# sparrow_ble.net
KiCad netlist of a schematic drawn in EAGLE
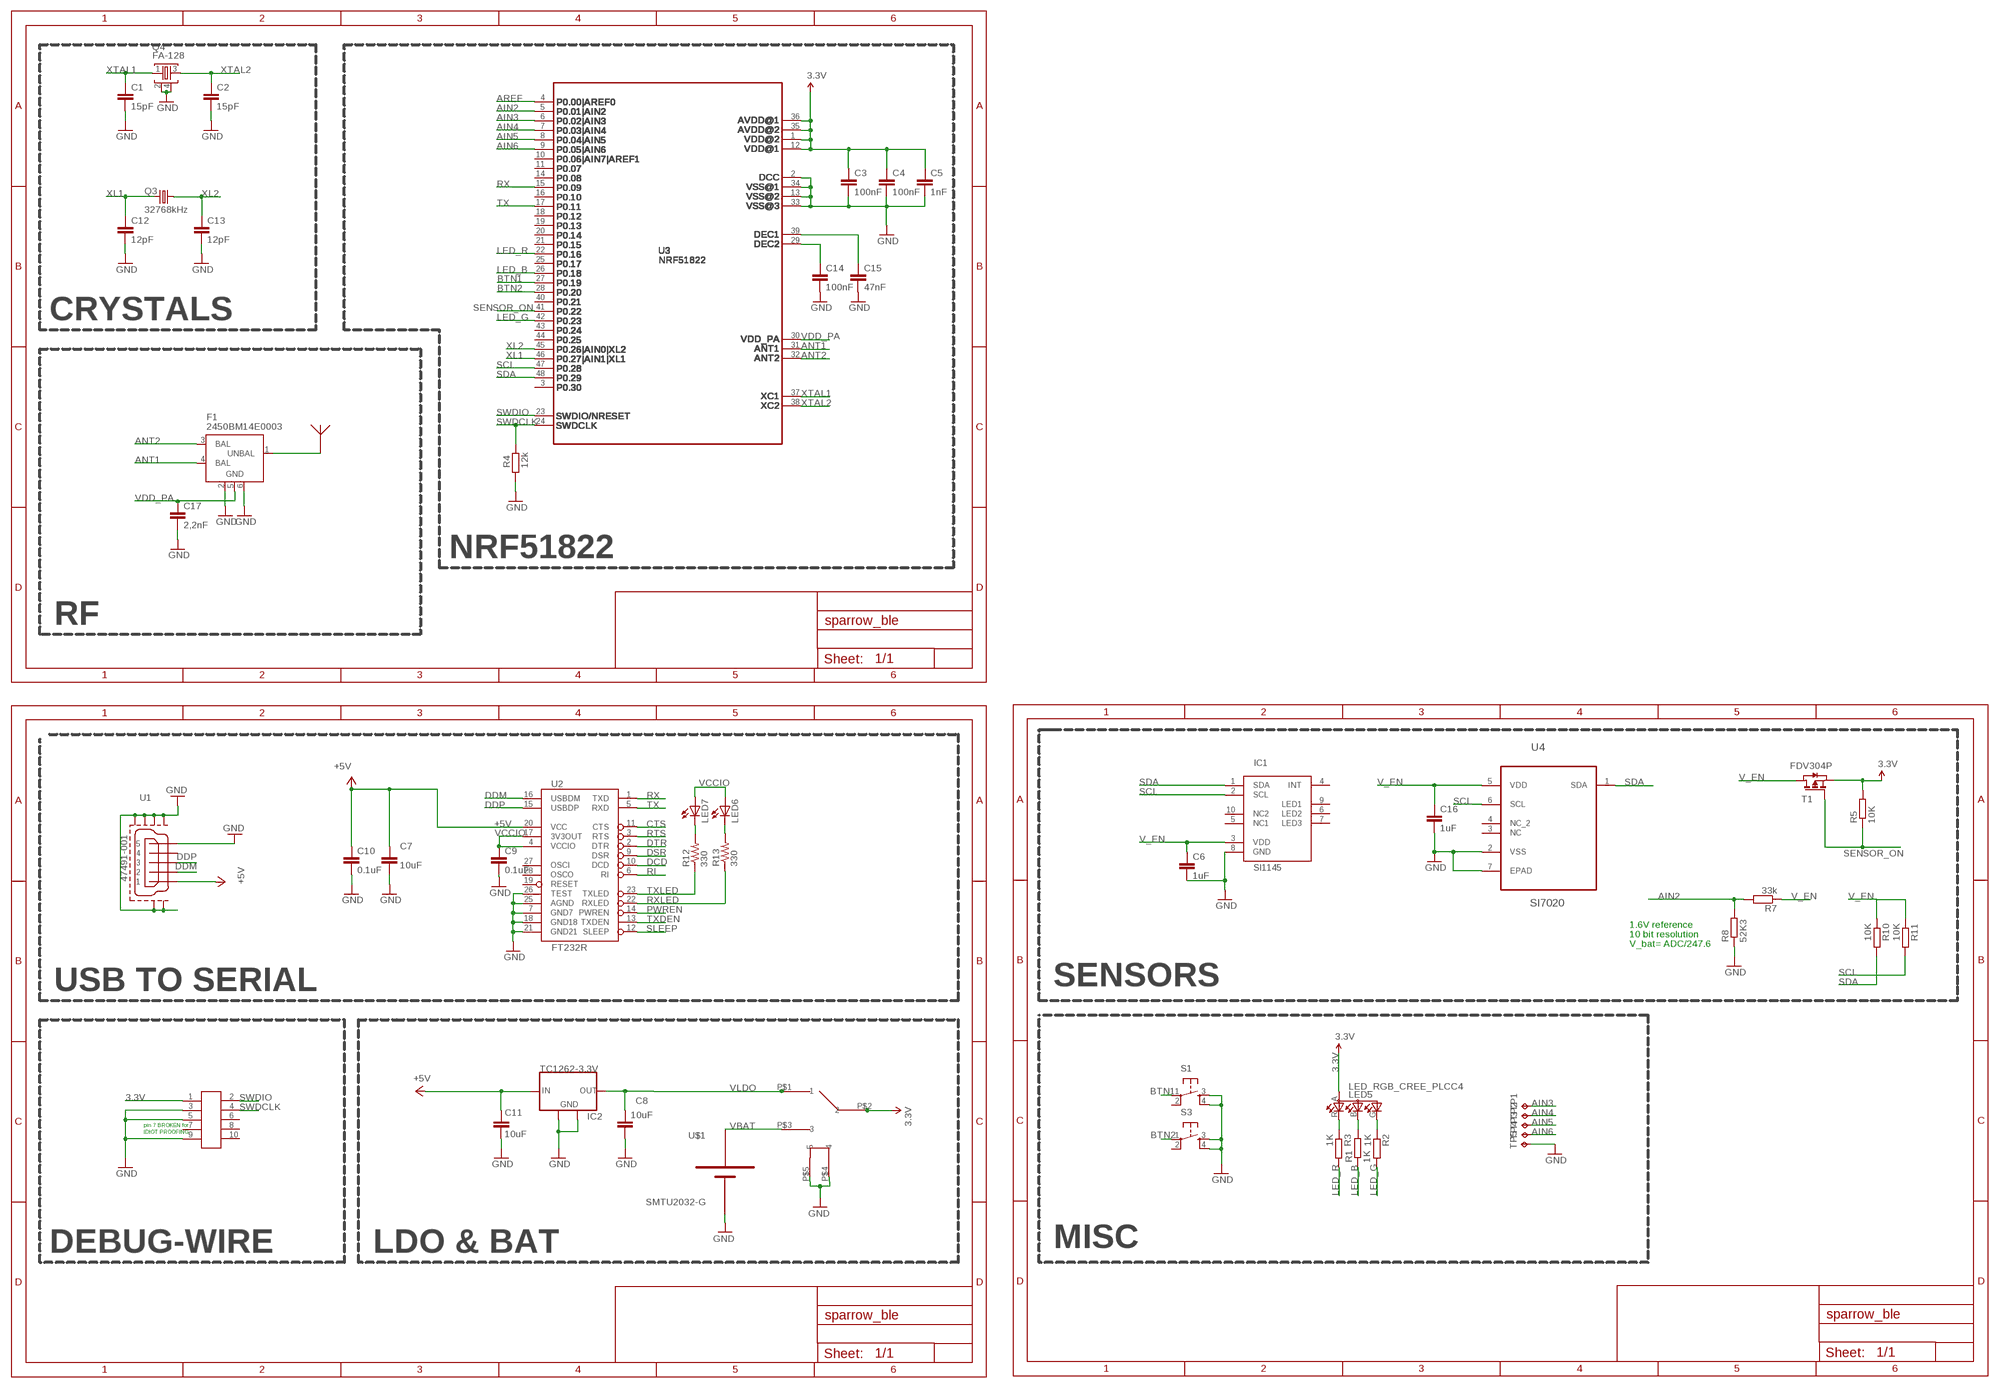
[diagram p0: schematic, sheet 1]

(export (version "E")
  (design (tool "Eeschema 10.0.6"))
  (components
    (comp (ref "C1")
      (value "15pF")
      (footprint "eagle-import:C0402")
      (libsource (lib "eagle-import") (part "resistor_C-EUC0402"))
    )
    (comp (ref "C2")
      (value "15pF")
      (footprint "eagle-import:C0402")
      (libsource (lib "eagle-import") (part "resistor_C-EUC0402"))
    )
    (comp (ref "C3")
      (value "100nF")
      (footprint "eagle-import:C0402")
      (libsource (lib "eagle-import") (part "resistor_C-EUC0402"))
    )
    (comp (ref "C4")
      (value "100nF")
      (footprint "eagle-import:C0402")
      (libsource (lib "eagle-import") (part "resistor_C-EUC0402"))
    )
    (comp (ref "C5")
      (value "1nF")
      (footprint "eagle-import:C0402")
      (libsource (lib "eagle-import") (part "resistor_C-EUC0402"))
    )
    (comp (ref "C6")
      (value "1uF")
      (footprint "eagle-import:C0402")
      (libsource (lib "eagle-import") (part "resistor_C-EUC0402"))
    )
    (comp (ref "C7")
      (value "10uF")
      (footprint "eagle-import:C0402")
      (libsource (lib "eagle-import") (part "C-EUC0402"))
    )
    (comp (ref "C8")
      (value "10uF")
      (footprint "eagle-import:C0402")
      (libsource (lib "eagle-import") (part "C-EUC0402"))
    )
    (comp (ref "C9")
      (value "0.1uF")
      (footprint "eagle-import:0402-CAP")
      (libsource (lib "eagle-import") (part "CAP0402-CAP"))
    )
    (comp (ref "C10")
      (value "0.1uF")
      (footprint "eagle-import:0402-CAP")
      (libsource (lib "eagle-import") (part "CAP0402-CAP"))
    )
    (comp (ref "C11")
      (value "10uF")
      (footprint "eagle-import:C0402")
      (libsource (lib "eagle-import") (part "C-EUC0402"))
    )
    (comp (ref "C12")
      (value "12pF")
      (footprint "eagle-import:C0402")
      (libsource (lib "eagle-import") (part "resistor_C-EUC0402"))
    )
    (comp (ref "C13")
      (value "12pF")
      (footprint "eagle-import:C0402")
      (libsource (lib "eagle-import") (part "resistor_C-EUC0402"))
    )
    (comp (ref "C14")
      (value "100nF")
      (footprint "eagle-import:C0402")
      (libsource (lib "eagle-import") (part "resistor_C-EUC0402"))
    )
    (comp (ref "C15")
      (value "47nF")
      (footprint "eagle-import:C0402")
      (libsource (lib "eagle-import") (part "resistor_C-EUC0402"))
    )
    (comp (ref "C16")
      (value "1uF")
      (footprint "eagle-import:C0402")
      (libsource (lib "eagle-import") (part "resistor_C-EUC0402"))
    )
    (comp (ref "C17")
      (value "2,2nF")
      (footprint "eagle-import:C0402")
      (libsource (lib "eagle-import") (part "resistor_C-EUC0402"))
    )
    (comp (ref "F1")
      (value "2450BM14E0003")
      (footprint "eagle-import:2450BM15A0002")
      (libsource (lib "eagle-import") (part "2450BM15A0002"))
    )
    (comp (ref "IC1")
      (value "SI1145")
      (footprint "eagle-import:QFN10")
      (libsource (lib "eagle-import") (part "SI1145"))
    )
    (comp (ref "IC2")
      (value "TC1262-3.3V")
      (footprint "eagle-import:SOT223")
      (libsource (lib "eagle-import") (part "MCP1825S-SOT223"))
    )
    (comp (ref "J3")
      (value "SMALL_HEADER_5X2")
      (footprint "eagle-import:SAMTEC_5X2")
      (libsource (lib "eagle-import") (part "SMALL_HEADER_5X2"))
    )
    (comp (ref "LED5")
      (value "LED_RGB_CREE_PLCC4")
      (footprint "eagle-import:P-LCC-4-4")
      (libsource (lib "eagle-import") (part "LED_RGB_CREE_PLCC4"))
    )
    (comp (ref "LED6")
      (value "LEDCHIP-LED0603")
      (footprint "eagle-import:CHIP-LED0603")
      (libsource (lib "eagle-import") (part "LEDCHIP-LED0603"))
    )
    (comp (ref "LED7")
      (value "LEDCHIP-LED0603")
      (footprint "eagle-import:CHIP-LED0603")
      (libsource (lib "eagle-import") (part "LEDCHIP-LED0603"))
    )
    (comp (ref "Q3")
      (value "32768kHz")
      (footprint "eagle-import:FC-12M")
      (libsource (lib "eagle-import") (part "FC-12M"))
    )
    (comp (ref "Q4")
      (value "FA-128")
      (footprint "eagle-import:FA-128")
      (libsource (lib "eagle-import") (part "FA-128"))
    )
    (comp (ref "R1")
      (value "1K")
      (footprint "eagle-import:R0402")
      (libsource (lib "eagle-import") (part "R-EU_R0402"))
    )
    (comp (ref "R2")
      (value "1K")
      (footprint "eagle-import:R0402")
      (libsource (lib "eagle-import") (part "R-EU_R0402"))
    )
    (comp (ref "R3")
      (value "1K")
      (footprint "eagle-import:R0402")
      (libsource (lib "eagle-import") (part "R-EU_R0402"))
    )
    (comp (ref "R4")
      (value "12k")
      (footprint "eagle-import:R0402")
      (libsource (lib "eagle-import") (part "resistor_R-EU_R0402"))
    )
    (comp (ref "R5")
      (value "10K")
      (footprint "eagle-import:R0402")
      (libsource (lib "eagle-import") (part "resistor_R-EU_R0402"))
    )
    (comp (ref "R7")
      (value "33k")
      (footprint "eagle-import:R0402")
      (libsource (lib "eagle-import") (part "resistor_R-EU_R0402"))
    )
    (comp (ref "R8")
      (value "52K3")
      (footprint "eagle-import:R0402")
      (libsource (lib "eagle-import") (part "resistor_R-EU_R0402"))
    )
    (comp (ref "R10")
      (value "10K")
      (footprint "eagle-import:R0402")
      (libsource (lib "eagle-import") (part "resistor_R-EU_R0402"))
    )
    (comp (ref "R11")
      (value "10K")
      (footprint "eagle-import:R0402")
      (libsource (lib "eagle-import") (part "resistor_R-EU_R0402"))
    )
    (comp (ref "R12")
      (value "330")
      (footprint "eagle-import:0402-RES")
      (libsource (lib "eagle-import") (part "RESISTOR0402-RES"))
    )
    (comp (ref "R13")
      (value "330")
      (footprint "eagle-import:0402-RES")
      (libsource (lib "eagle-import") (part "RESISTOR0402-RES"))
    )
    (comp (ref "S1")
      (value "TAC_SWITCHSMD")
      (footprint "eagle-import:TACTILE-SWITCH-SMD")
      (libsource (lib "eagle-import") (part "TAC_SWITCHSMD"))
    )
    (comp (ref "S3")
      (value "TAC_SWITCHSMD")
      (footprint "eagle-import:TACTILE-SWITCH-SMD")
      (libsource (lib "eagle-import") (part "TAC_SWITCHSMD"))
    )
    (comp (ref "T1")
      (value "FDV304P")
      (footprint "eagle-import:SOT-23")
      (libsource (lib "eagle-import") (part "PMOSSOT23"))
    )
    (comp (ref "TP1")
      (value "TPTP16R")
      (footprint "eagle-import:TP16R")
      (libsource (lib "eagle-import") (part "TPTP16R"))
    )
    (comp (ref "TP2")
      (value "TPTP16R")
      (footprint "eagle-import:TP16R")
      (libsource (lib "eagle-import") (part "TPTP16R"))
    )
    (comp (ref "TP3")
      (value "TPTP16R")
      (footprint "eagle-import:TP16R")
      (libsource (lib "eagle-import") (part "TPTP16R"))
    )
    (comp (ref "TP4")
      (value "TPTP16R")
      (footprint "eagle-import:TP16R")
      (libsource (lib "eagle-import") (part "TPTP16R"))
    )
    (comp (ref "TP5")
      (value "TPTP16R")
      (footprint "eagle-import:TP16R")
      (libsource (lib "eagle-import") (part "TPTP16R"))
    )
    (comp (ref "U$1")
      (value "SMTU2032-G")
      (footprint "eagle-import:SMTU2032-G")
      (libsource (lib "eagle-import") (part "SMTU2032-G"))
    )
    (comp (ref "U$2")
      (value "SWITCH")
      (footprint "eagle-import:PCM12")
      (libsource (lib "eagle-import") (part "SWITCH"))
    )
    (comp (ref "U1")
      (value "47491-001")
      (footprint "eagle-import:47491-0001")
      (libsource (lib "eagle-import") (part "47491-001"))
    )
    (comp (ref "U2")
      (value "FT232R")
      (footprint "eagle-import:SSOP28DB")
      (libsource (lib "eagle-import") (part "FT232RLSSOP"))
    )
    (comp (ref "U3")
      (value "NRF51822")
      (footprint "eagle-import:NRF51822-QFN48")
      (libsource (lib "eagle-import") (part "NRF51822"))
    )
    (comp (ref "U4")
      (value "SI7020")
      (footprint "eagle-import:DFN300X300X110-7N")
      (fields (field (name "MPN") "SHT21"))
      (libsource (lib "eagle-import") (part "SHT21"))
    )
    (comp (ref "U8")
      (value "ANTENNA")
      (footprint "eagle-import:ANTPACK")
      (libsource (lib "eagle-import") (part "ANTENNA"))
    )
  )
  (nets
    (net (code "1") (name "+5V") (class "Default")
      (node (ref "C10") (pin "1") (pinfunction "1_1") (pintype "passive"))
      (node (ref "C11") (pin "1") (pinfunction "1_1") (pintype "passive"))
      (node (ref "C7") (pin "1") (pinfunction "1_1") (pintype "passive"))
      (node (ref "IC2") (pin "1") (pinfunction "IN_1") (pintype "input"))
      (node (ref "U1") (pin "1") (pinfunction "1_1") (pintype "input"))
      (node (ref "U2") (pin "20") (pinfunction "VCC_20") (pintype "power_in"))
    )
    (net (code "2") (name "/AIN2") (class "Default")
      (node (ref "R7") (pin "2") (pinfunction "2_2") (pintype "passive"))
      (node (ref "R8") (pin "2") (pinfunction "2_2") (pintype "passive"))
      (node (ref "U3") (pin "5") (pinfunction "1_5") (pintype "bidirectional"))
    )
    (net (code "3") (name "/AIN3") (class "Default")
      (node (ref "TP1") (pin "TP") (pinfunction "TP_TP") (pintype "input"))
      (node (ref "U3") (pin "6") (pinfunction "1_6") (pintype "bidirectional"))
    )
    (net (code "4") (name "/AIN4") (class "Default")
      (node (ref "TP2") (pin "TP") (pinfunction "TP_TP") (pintype "input"))
      (node (ref "U3") (pin "7") (pinfunction "1_7") (pintype "bidirectional"))
    )
    (net (code "5") (name "/AIN5") (class "Default")
      (node (ref "TP3") (pin "TP") (pinfunction "TP_TP") (pintype "input"))
      (node (ref "U3") (pin "8") (pinfunction "1_8") (pintype "bidirectional"))
    )
    (net (code "6") (name "/AIN6") (class "Default")
      (node (ref "TP4") (pin "TP") (pinfunction "TP_TP") (pintype "input"))
      (node (ref "U3") (pin "9") (pinfunction "1_9") (pintype "bidirectional"))
    )
    (net (code "7") (name "/ANT1") (class "Default")
      (node (ref "F1") (pin "4") (pinfunction "BAL_4") (pintype "passive"))
      (node (ref "U3") (pin "31") (pinfunction "1_31") (pintype "bidirectional"))
    )
    (net (code "8") (name "/ANT2") (class "Default")
      (node (ref "F1") (pin "3") (pinfunction "BAL_3") (pintype "passive"))
      (node (ref "U3") (pin "32") (pinfunction "1_32") (pintype "bidirectional"))
    )
    (net (code "9") (name "/AREF") (class "Default")
      (node (ref "U3") (pin "4") (pinfunction "1_4") (pintype "bidirectional"))
    )
    (net (code "10") (name "/BTN1") (class "Default")
      (node (ref "S1") (pin "1") (pinfunction "1_1") (pintype "passive"))
      (node (ref "U3") (pin "27") (pinfunction "1_27") (pintype "bidirectional"))
    )
    (net (code "11") (name "/BTN2") (class "Default")
      (node (ref "S3") (pin "1") (pinfunction "1_1") (pintype "passive"))
      (node (ref "U3") (pin "28") (pinfunction "1_28") (pintype "bidirectional"))
    )
    (net (code "12") (name "/CTS") (class "Default")
      (node (ref "U2") (pin "11") (pinfunction "CTS_11") (pintype "input"))
    )
    (net (code "13") (name "/DCD") (class "Default")
      (node (ref "U2") (pin "10") (pinfunction "DCD_10") (pintype "input"))
    )
    (net (code "14") (name "/DDM") (class "Default")
      (node (ref "U1") (pin "2") (pinfunction "2_2") (pintype "input"))
      (node (ref "U2") (pin "16") (pinfunction "USBDM_16") (pintype "bidirectional"))
    )
    (net (code "15") (name "/DDP") (class "Default")
      (node (ref "U1") (pin "3") (pinfunction "3_3") (pintype "input"))
      (node (ref "U2") (pin "15") (pinfunction "USBDP_15") (pintype "bidirectional"))
    )
    (net (code "16") (name "/DSR") (class "Default")
      (node (ref "U2") (pin "9") (pinfunction "DSR_9") (pintype "input"))
    )
    (net (code "17") (name "/DTR") (class "Default")
      (node (ref "U2") (pin "2") (pinfunction "DTR_2") (pintype "output"))
    )
    (net (code "18") (name "/LED_B") (class "Default")
      (node (ref "R1") (pin "1") (pinfunction "1_1") (pintype "passive"))
      (node (ref "U3") (pin "26") (pinfunction "1_26") (pintype "bidirectional"))
    )
    (net (code "19") (name "/LED_G") (class "Default")
      (node (ref "R2") (pin "2") (pinfunction "2_2") (pintype "passive"))
      (node (ref "U3") (pin "42") (pinfunction "1_42") (pintype "bidirectional"))
    )
    (net (code "20") (name "/LED_R") (class "Default")
      (node (ref "R3") (pin "2") (pinfunction "2_2") (pintype "passive"))
      (node (ref "U3") (pin "22") (pinfunction "1_22") (pintype "bidirectional"))
    )
    (net (code "21") (name "/PWREN") (class "Default")
      (node (ref "U2") (pin "14") (pinfunction "PWREN_14") (pintype "input"))
    )
    (net (code "22") (name "/RI") (class "Default")
      (node (ref "U2") (pin "6") (pinfunction "RI_6") (pintype "input"))
    )
    (net (code "23") (name "/RTS") (class "Default")
      (node (ref "U2") (pin "3") (pinfunction "RTS_3") (pintype "output"))
    )
    (net (code "24") (name "/RX") (class "Default")
      (node (ref "U2") (pin "1") (pinfunction "TXD_1") (pintype "output"))
      (node (ref "U3") (pin "15") (pinfunction "1_15") (pintype "bidirectional"))
    )
    (net (code "25") (name "/RXLED") (class "Default")
      (node (ref "R13") (pin "1") (pinfunction "1_1") (pintype "passive"))
      (node (ref "U2") (pin "22") (pinfunction "RXLED_22") (pintype "input"))
    )
    (net (code "26") (name "/SCL") (class "Default")
      (node (ref "IC1") (pin "2") (pinfunction "SCL_2") (pintype "bidirectional"))
      (node (ref "R11") (pin "2") (pinfunction "2_2") (pintype "passive"))
      (node (ref "U3") (pin "47") (pinfunction "1_47") (pintype "bidirectional"))
      (node (ref "U4") (pin "6") (pinfunction "SCL_6") (pintype "input"))
    )
    (net (code "27") (name "/SDA") (class "Default")
      (node (ref "IC1") (pin "1") (pinfunction "SDA_1") (pintype "bidirectional"))
      (node (ref "R10") (pin "2") (pinfunction "2_2") (pintype "passive"))
      (node (ref "U3") (pin "48") (pinfunction "1_48") (pintype "bidirectional"))
      (node (ref "U4") (pin "1") (pinfunction "SDA_1") (pintype "bidirectional"))
    )
    (net (code "28") (name "/SENSOR_ON") (class "Default")
      (node (ref "R5") (pin "1") (pinfunction "1_1") (pintype "passive"))
      (node (ref "T1") (pin "3") (pinfunction "G_3") (pintype "passive"))
      (node (ref "U3") (pin "41") (pinfunction "1_41") (pintype "bidirectional"))
    )
    (net (code "29") (name "/SLEEP") (class "Default")
      (node (ref "U2") (pin "12") (pinfunction "SLEEP_12") (pintype "input"))
    )
    (net (code "30") (name "/SWDCLK") (class "Default")
      (node (ref "J3") (pin "4") (pinfunction "P$4_4") (pintype "bidirectional"))
      (node (ref "R4") (pin "2") (pinfunction "2_2") (pintype "passive"))
      (node (ref "U3") (pin "24") (pinfunction "1_24") (pintype "bidirectional"))
    )
    (net (code "31") (name "/SWDIO") (class "Default")
      (node (ref "J3") (pin "2") (pinfunction "P$2_2") (pintype "bidirectional"))
      (node (ref "U3") (pin "23") (pinfunction "1_23") (pintype "bidirectional"))
    )
    (net (code "32") (name "/TX") (class "Default")
      (node (ref "U2") (pin "5") (pinfunction "RXD_5") (pintype "input"))
      (node (ref "U3") (pin "17") (pinfunction "1_17") (pintype "bidirectional"))
    )
    (net (code "33") (name "/TXDEN") (class "Default")
      (node (ref "U2") (pin "13") (pinfunction "TXDEN_13") (pintype "input"))
    )
    (net (code "34") (name "/TXLED") (class "Default")
      (node (ref "R12") (pin "1") (pinfunction "1_1") (pintype "passive"))
      (node (ref "U2") (pin "23") (pinfunction "TXLED_23") (pintype "input"))
    )
    (net (code "35") (name "/VBAT") (class "Default")
      (node (ref "U$1") (pin "1") (pinfunction "P$1_1") (pintype "bidirectional"))
      (node (ref "U$2") (pin "P$3") (pinfunction "3_P$3") (pintype "bidirectional"))
    )
    (net (code "36") (name "/VCCIO") (class "Default")
      (node (ref "C9") (pin "1") (pinfunction "1_1") (pintype "passive"))
      (node (ref "LED6") (pin "A") (pinfunction "A_A") (pintype "passive"))
      (node (ref "LED7") (pin "A") (pinfunction "A_A") (pintype "passive"))
      (node (ref "U2") (pin "17") (pinfunction "3V3OUT_17") (pintype "output"))
      (node (ref "U2") (pin "4") (pinfunction "VCCIO_4") (pintype "power_in"))
    )
    (net (code "37") (name "/VDD_PA") (class "Default")
      (node (ref "C17") (pin "1") (pinfunction "1_1") (pintype "passive"))
      (node (ref "F1") (pin "5") (pinfunction "GND_5") (pintype "passive"))
      (node (ref "U3") (pin "30") (pinfunction "1_30") (pintype "output"))
    )
    (net (code "38") (name "/VLDO") (class "Default")
      (node (ref "C8") (pin "1") (pinfunction "1_1") (pintype "passive"))
      (node (ref "IC2") (pin "3") (pinfunction "OUT_3") (pintype "output"))
      (node (ref "U$2") (pin "P$1") (pinfunction "1_P$1") (pintype "bidirectional"))
    )
    (net (code "39") (name "/V_EN") (class "Default")
      (node (ref "C16") (pin "1") (pinfunction "1_1") (pintype "passive"))
      (node (ref "C6") (pin "1") (pinfunction "1_1") (pintype "passive"))
      (node (ref "IC1") (pin "3") (pinfunction "VDD_3") (pintype "bidirectional"))
      (node (ref "R10") (pin "1") (pinfunction "1_1") (pintype "passive"))
      (node (ref "R11") (pin "1") (pinfunction "1_1") (pintype "passive"))
      (node (ref "R7") (pin "1") (pinfunction "1_1") (pintype "passive"))
      (node (ref "T1") (pin "1") (pinfunction "D_1") (pintype "passive"))
      (node (ref "U4") (pin "5") (pinfunction "VDD_5") (pintype "power_in"))
    )
    (net (code "40") (name "/XL1") (class "Default")
      (node (ref "C12") (pin "1") (pinfunction "1_1") (pintype "passive"))
      (node (ref "Q3") (pin "2") (pinfunction "2_2") (pintype "passive"))
      (node (ref "U3") (pin "46") (pinfunction "1_46") (pintype "bidirectional"))
    )
    (net (code "41") (name "/XL2") (class "Default")
      (node (ref "C13") (pin "1") (pinfunction "1_1") (pintype "passive"))
      (node (ref "Q3") (pin "1") (pinfunction "1_1") (pintype "passive"))
      (node (ref "U3") (pin "45") (pinfunction "1_45") (pintype "bidirectional"))
    )
    (net (code "42") (name "/XTAL1") (class "Default")
      (node (ref "C1") (pin "1") (pinfunction "1_1") (pintype "passive"))
      (node (ref "Q4") (pin "1") (pinfunction "1_1") (pintype "passive"))
      (node (ref "U3") (pin "37") (pinfunction "1_37") (pintype "bidirectional"))
    )
    (net (code "43") (name "/XTAL2") (class "Default")
      (node (ref "C2") (pin "1") (pinfunction "1_1") (pintype "passive"))
      (node (ref "Q4") (pin "3") (pinfunction "3_3") (pintype "passive"))
      (node (ref "U3") (pin "38") (pinfunction "1_38") (pintype "bidirectional"))
    )
    (net (code "44") (name "3.3V") (class "Default")
      (node (ref "C3") (pin "1") (pinfunction "1_1") (pintype "passive"))
      (node (ref "C4") (pin "1") (pinfunction "1_1") (pintype "passive"))
      (node (ref "C5") (pin "1") (pinfunction "1_1") (pintype "passive"))
      (node (ref "J3") (pin "1") (pinfunction "P$1_1") (pintype "bidirectional"))
      (node (ref "LED5") (pin "A") (pinfunction "A2_A") (pintype "passive"))
      (node (ref "R5") (pin "2") (pinfunction "2_2") (pintype "passive"))
      (node (ref "T1") (pin "2") (pinfunction "S_2") (pintype "passive"))
      (node (ref "U$2") (pin "P$2") (pinfunction "2_P$2") (pintype "bidirectional"))
      (node (ref "U3") (pin "1") (pinfunction "1_1") (pintype "input"))
      (node (ref "U3") (pin "12") (pinfunction "1_12") (pintype "input"))
      (node (ref "U3") (pin "35") (pinfunction "1_35") (pintype "input"))
      (node (ref "U3") (pin "36") (pinfunction "1_36") (pintype "input"))
    )
    (net (code "45") (name "GND") (class "Default")
      (node (ref "C1") (pin "2") (pinfunction "2_2") (pintype "passive"))
      (node (ref "C10") (pin "2") (pinfunction "2_2") (pintype "passive"))
      (node (ref "C11") (pin "2") (pinfunction "2_2") (pintype "passive"))
      (node (ref "C12") (pin "2") (pinfunction "2_2") (pintype "passive"))
      (node (ref "C13") (pin "2") (pinfunction "2_2") (pintype "passive"))
      (node (ref "C14") (pin "2") (pinfunction "2_2") (pintype "passive"))
      (node (ref "C15") (pin "2") (pinfunction "2_2") (pintype "passive"))
      (node (ref "C16") (pin "2") (pinfunction "2_2") (pintype "passive"))
      (node (ref "C17") (pin "2") (pinfunction "2_2") (pintype "passive"))
      (node (ref "C2") (pin "2") (pinfunction "2_2") (pintype "passive"))
      (node (ref "C3") (pin "2") (pinfunction "2_2") (pintype "passive"))
      (node (ref "C4") (pin "2") (pinfunction "2_2") (pintype "passive"))
      (node (ref "C5") (pin "2") (pinfunction "2_2") (pintype "passive"))
      (node (ref "C6") (pin "2") (pinfunction "2_2") (pintype "passive"))
      (node (ref "C7") (pin "2") (pinfunction "2_2") (pintype "passive"))
      (node (ref "C8") (pin "2") (pinfunction "2_2") (pintype "passive"))
      (node (ref "C9") (pin "2") (pinfunction "2_2") (pintype "passive"))
      (node (ref "F1") (pin "2") (pinfunction "GND_2") (pintype "passive"))
      (node (ref "F1") (pin "6") (pinfunction "GND_6") (pintype "passive"))
      (node (ref "IC1") (pin "8") (pinfunction "GND_8") (pintype "bidirectional"))
      (node (ref "IC2") (pin "2") (pinfunction "GND_2") (pintype "power_in"))
      (node (ref "IC2") (pin "4") (pinfunction "GND_4") (pintype "power_in"))
      (node (ref "J3") (pin "3") (pinfunction "P$3_3") (pintype "bidirectional"))
      (node (ref "J3") (pin "5") (pinfunction "P$5_5") (pintype "bidirectional"))
      (node (ref "J3") (pin "9") (pinfunction "P$9_9") (pintype "bidirectional"))
      (node (ref "Q4") (pin "2") (pinfunction "2_2") (pintype "passive"))
      (node (ref "Q4") (pin "4") (pinfunction "4_4") (pintype "passive"))
      (node (ref "R4") (pin "1") (pinfunction "1_1") (pintype "passive"))
      (node (ref "R8") (pin "1") (pinfunction "1_1") (pintype "passive"))
      (node (ref "S1") (pin "3") (pinfunction "3_3") (pintype "passive"))
      (node (ref "S1") (pin "4") (pinfunction "4_4") (pintype "passive"))
      (node (ref "S3") (pin "3") (pinfunction "3_3") (pintype "passive"))
      (node (ref "S3") (pin "4") (pinfunction "4_4") (pintype "passive"))
      (node (ref "TP5") (pin "TP") (pinfunction "TP_TP") (pintype "input"))
      (node (ref "U$1") (pin "2") (pinfunction "P$2_2") (pintype "bidirectional"))
      (node (ref "U$2") (pin "P$4") (pinfunction "4_P$4") (pintype "bidirectional"))
      (node (ref "U$2") (pin "P$5") (pinfunction "5_P$5") (pintype "bidirectional"))
      (node (ref "U1") (pin "5") (pinfunction "5_5") (pintype "input"))
      (node (ref "U1") (pin "GND1") (pinfunction "GND1_GND1") (pintype "bidirectional"))
      (node (ref "U1") (pin "GND2") (pinfunction "GND2_GND2") (pintype "bidirectional"))
      (node (ref "U1") (pin "GND3") (pinfunction "GND3_GND3") (pintype "bidirectional"))
      (node (ref "U1") (pin "GND4") (pinfunction "GND4_GND4") (pintype "bidirectional"))
      (node (ref "U1") (pin "GND5") (pinfunction "GND5_GND5") (pintype "bidirectional"))
      (node (ref "U1") (pin "GND6") (pinfunction "GND6_GND6") (pintype "bidirectional"))
      (node (ref "U2") (pin "18") (pinfunction "GND18_18") (pintype "power_in"))
      (node (ref "U2") (pin "21") (pinfunction "GND21_21") (pintype "power_in"))
      (node (ref "U2") (pin "25") (pinfunction "AGND_25") (pintype "power_in"))
      (node (ref "U2") (pin "26") (pinfunction "TEST_26") (pintype "input"))
      (node (ref "U2") (pin "7") (pinfunction "GND7_7") (pintype "power_in"))
      (node (ref "U3") (pin "13") (pinfunction "1_13") (pintype "input"))
      (node (ref "U3") (pin "2") (pinfunction "1_2") (pintype "input"))
      (node (ref "U3") (pin "33") (pinfunction "1_33") (pintype "input"))
      (node (ref "U3") (pin "34") (pinfunction "1_34") (pintype "input"))
      (node (ref "U4") (pin "2") (pinfunction "VSS_2") (pintype "power_in"))
      (node (ref "U4") (pin "7") (pinfunction "EPAD_7") (pintype "passive"))
    )
    (net (code "46") (name "Net-(F1-UNBAL)") (class "Default")
      (node (ref "F1") (pin "1") (pinfunction "UNBAL_1") (pintype "passive"))
      (node (ref "U8") (pin "P$1") (pinfunction "P$1_P$1") (pintype "bidirectional"))
    )
    (net (code "47") (name "Net-(LED5-CBLUE)") (class "Default")
      (node (ref "LED5") (pin "B") (pinfunction "CBLUE_B") (pintype "passive"))
      (node (ref "R1") (pin "2") (pinfunction "2_2") (pintype "passive"))
    )
    (net (code "48") (name "Net-(LED5-CGREEN)") (class "Default")
      (node (ref "LED5") (pin "G") (pinfunction "CGREEN_G") (pintype "passive"))
      (node (ref "R2") (pin "1") (pinfunction "1_1") (pintype "passive"))
    )
    (net (code "49") (name "Net-(LED5-CRED)") (class "Default")
      (node (ref "LED5") (pin "R") (pinfunction "CRED_R") (pintype "passive"))
      (node (ref "R3") (pin "1") (pinfunction "1_1") (pintype "passive"))
    )
    (net (code "50") (name "Net-(LED6-PadC)") (class "Default")
      (node (ref "LED6") (pin "C") (pinfunction "C_C") (pintype "passive"))
      (node (ref "R13") (pin "2") (pinfunction "2_2") (pintype "passive"))
    )
    (net (code "51") (name "Net-(LED7-PadC)") (class "Default")
      (node (ref "LED7") (pin "C") (pinfunction "C_C") (pintype "passive"))
      (node (ref "R12") (pin "2") (pinfunction "2_2") (pintype "passive"))
    )
    (net (code "52") (name "Net-(U3F-1)") (class "Default")
      (node (ref "C15") (pin "1") (pinfunction "1_1") (pintype "passive"))
      (node (ref "U3") (pin "39") (pinfunction "1_39") (pintype "output"))
    )
    (net (code "53") (name "Net-(U3G-1)") (class "Default")
      (node (ref "C14") (pin "1") (pinfunction "1_1") (pintype "passive"))
      (node (ref "U3") (pin "29") (pinfunction "1_29") (pintype "output"))
    )
    (net (code "54") (name "unconnected-(IC1-INT-Pad4)") (class "Default")
      (node (ref "IC1") (pin "4") (pinfunction "INT_4") (pintype "bidirectional"))
    )
    (net (code "55") (name "unconnected-(IC1-LED1-Pad9)") (class "Default")
      (node (ref "IC1") (pin "9") (pinfunction "LED1_9") (pintype "bidirectional"))
    )
    (net (code "56") (name "unconnected-(IC1-LED2-Pad6)") (class "Default")
      (node (ref "IC1") (pin "6") (pinfunction "LED2_6") (pintype "bidirectional"))
    )
    (net (code "57") (name "unconnected-(IC1-LED3-Pad7)") (class "Default")
      (node (ref "IC1") (pin "7") (pinfunction "LED3_7") (pintype "bidirectional"))
    )
    (net (code "58") (name "unconnected-(IC1-NC1-Pad5)") (class "Default")
      (node (ref "IC1") (pin "5") (pinfunction "NC1_5") (pintype "no_connect"))
    )
    (net (code "59") (name "unconnected-(IC1-NC2-Pad10)") (class "Default")
      (node (ref "IC1") (pin "10") (pinfunction "NC2_10") (pintype "no_connect"))
    )
    (net (code "60") (name "unconnected-(J3-P$6-Pad6)") (class "Default")
      (node (ref "J3") (pin "6") (pinfunction "P$6_6") (pintype "bidirectional"))
    )
    (net (code "61") (name "unconnected-(J3-P$7-Pad7)") (class "Default")
      (node (ref "J3") (pin "7") (pinfunction "P$7_7") (pintype "bidirectional"))
    )
    (net (code "62") (name "unconnected-(J3-P$8-Pad8)") (class "Default")
      (node (ref "J3") (pin "8") (pinfunction "P$8_8") (pintype "bidirectional"))
    )
    (net (code "63") (name "unconnected-(J3-P$10-Pad10)") (class "Default")
      (node (ref "J3") (pin "10") (pinfunction "P$10_10") (pintype "bidirectional"))
    )
    (net (code "64") (name "unconnected-(S1-Pad2)") (class "Default")
      (node (ref "S1") (pin "2") (pinfunction "2_2") (pintype "passive"))
    )
    (net (code "65") (name "unconnected-(S3-Pad2)") (class "Default")
      (node (ref "S3") (pin "2") (pinfunction "2_2") (pintype "passive"))
    )
    (net (code "66") (name "unconnected-(U1-Pad4)") (class "Default")
      (node (ref "U1") (pin "4") (pinfunction "4_4") (pintype "input"))
    )
    (net (code "67") (name "unconnected-(U2-OSCI-Pad27)") (class "Default")
      (node (ref "U2") (pin "27") (pinfunction "OSCI_27") (pintype "input"))
    )
    (net (code "68") (name "unconnected-(U2-OSCO-Pad28)") (class "Default")
      (node (ref "U2") (pin "28") (pinfunction "OSCO_28") (pintype "output"))
    )
    (net (code "69") (name "unconnected-(U2-RESET-Pad19)") (class "Default")
      (node (ref "U2") (pin "19") (pinfunction "RESET_19") (pintype "input"))
    )
    (net (code "70") (name "unconnected-(U3AC-1-Pad40)") (class "Default")
      (node (ref "U3") (pin "40") (pinfunction "1_40") (pintype "bidirectional"))
    )
    (net (code "71") (name "unconnected-(U3AF-1-Pad43)") (class "Default")
      (node (ref "U3") (pin "43") (pinfunction "1_43") (pintype "bidirectional"))
    )
    (net (code "72") (name "unconnected-(U3AG-1-Pad44)") (class "Default")
      (node (ref "U3") (pin "44") (pinfunction "1_44") (pintype "bidirectional"))
    )
    (net (code "73") (name "unconnected-(U3AL-1-Pad3)") (class "Default")
      (node (ref "U3") (pin "3") (pinfunction "1_3") (pintype "bidirectional"))
    )
    (net (code "74") (name "unconnected-(U3N-1-Pad10)") (class "Default")
      (node (ref "U3") (pin "10") (pinfunction "1_10") (pintype "bidirectional"))
    )
    (net (code "75") (name "unconnected-(U3O-1-Pad11)") (class "Default")
      (node (ref "U3") (pin "11") (pinfunction "1_11") (pintype "bidirectional"))
    )
    (net (code "76") (name "unconnected-(U3P-1-Pad14)") (class "Default")
      (node (ref "U3") (pin "14") (pinfunction "1_14") (pintype "bidirectional"))
    )
    (net (code "77") (name "unconnected-(U3R-1-Pad16)") (class "Default")
      (node (ref "U3") (pin "16") (pinfunction "1_16") (pintype "bidirectional"))
    )
    (net (code "78") (name "unconnected-(U3T-1-Pad18)") (class "Default")
      (node (ref "U3") (pin "18") (pinfunction "1_18") (pintype "bidirectional"))
    )
    (net (code "79") (name "unconnected-(U3U-1-Pad19)") (class "Default")
      (node (ref "U3") (pin "19") (pinfunction "1_19") (pintype "bidirectional"))
    )
    (net (code "80") (name "unconnected-(U3V-1-Pad20)") (class "Default")
      (node (ref "U3") (pin "20") (pinfunction "1_20") (pintype "bidirectional"))
    )
    (net (code "81") (name "unconnected-(U3W-1-Pad21)") (class "Default")
      (node (ref "U3") (pin "21") (pinfunction "1_21") (pintype "bidirectional"))
    )
    (net (code "82") (name "unconnected-(U3Y-1-Pad25)") (class "Default")
      (node (ref "U3") (pin "25") (pinfunction "1_25") (pintype "bidirectional"))
    )
    (net (code "83") (name "unconnected-(U4-NC-Pad3)") (class "Default")
      (node (ref "U4") (pin "3") (pinfunction "NC_3") (pintype "no_connect"))
    )
    (net (code "84") (name "unconnected-(U4-NC_2-Pad4)") (class "Default")
      (node (ref "U4") (pin "4") (pinfunction "NC_2_4") (pintype "no_connect"))
    )
  )
)
